# CDCEmu_v4_0.net
KiCad netlist of a schematic drawn in EAGLE
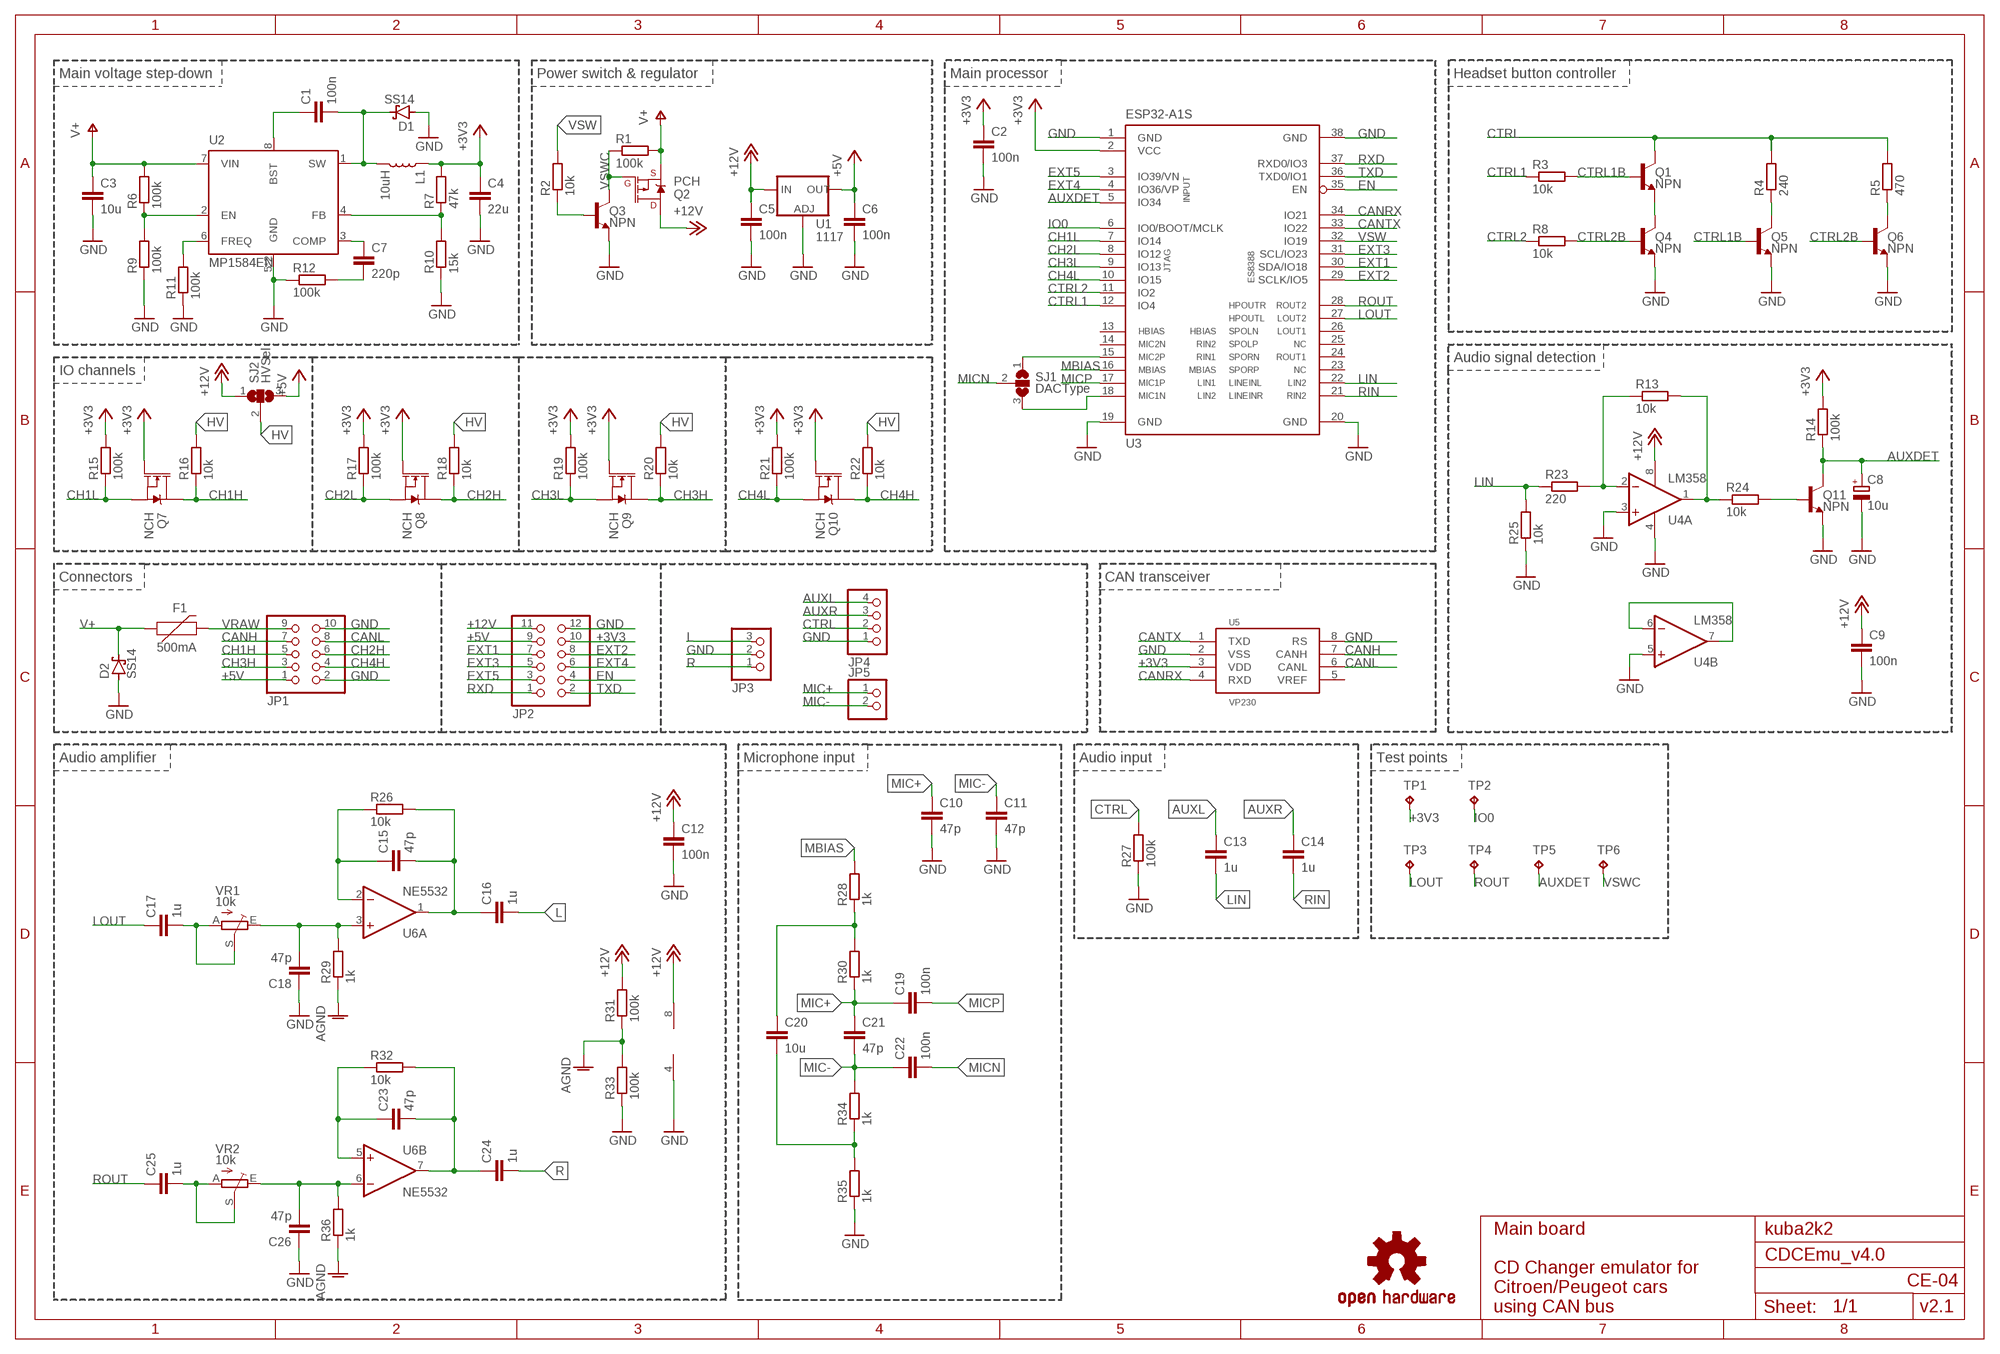
[diagram p0: schematic, sheet 1]

(export (version "E")
  (design (tool "Eeschema 10.0.6"))
  (components
    (comp (ref "C1")
      (value "100n")
      (footprint "eagle-import:C0805")
      (libsource (lib "eagle-import") (part "C-EUC0805"))
    )
    (comp (ref "C2")
      (value "100n")
      (footprint "eagle-import:C0805")
      (libsource (lib "eagle-import") (part "C-EUC0805"))
    )
    (comp (ref "C3")
      (value "10u")
      (footprint "eagle-import:C1206")
      (libsource (lib "eagle-import") (part "C-EUC1206"))
    )
    (comp (ref "C4")
      (value "22u")
      (footprint "eagle-import:C1206")
      (libsource (lib "eagle-import") (part "C-EUC1206"))
    )
    (comp (ref "C5")
      (value "100n")
      (footprint "eagle-import:C0805")
      (libsource (lib "eagle-import") (part "C-EUC0805"))
    )
    (comp (ref "C6")
      (value "100n")
      (footprint "eagle-import:C0805")
      (libsource (lib "eagle-import") (part "C-EUC0805"))
    )
    (comp (ref "C7")
      (value "220p")
      (footprint "eagle-import:C0805")
      (libsource (lib "eagle-import") (part "C-EUC0805"))
    )
    (comp (ref "C8")
      (value "10u")
      (footprint "eagle-import:C1206-POL")
      (libsource (lib "eagle-import") (part "CPOL-EUC1206"))
    )
    (comp (ref "C9")
      (value "100n")
      (footprint "eagle-import:C0805")
      (libsource (lib "eagle-import") (part "C-EUC0805"))
    )
    (comp (ref "C10")
      (value "47p")
      (footprint "eagle-import:C0805")
      (libsource (lib "eagle-import") (part "C-EUC0805"))
    )
    (comp (ref "C11")
      (value "47p")
      (footprint "eagle-import:C0805")
      (libsource (lib "eagle-import") (part "C-EUC0805"))
    )
    (comp (ref "C12")
      (value "100n")
      (footprint "eagle-import:C0805")
      (libsource (lib "eagle-import") (part "C-EUC0805"))
    )
    (comp (ref "C13")
      (value "1u")
      (footprint "eagle-import:C0805")
      (libsource (lib "eagle-import") (part "C-EUC0805"))
    )
    (comp (ref "C14")
      (value "1u")
      (footprint "eagle-import:C0805")
      (libsource (lib "eagle-import") (part "C-EUC0805"))
    )
    (comp (ref "C15")
      (value "47p")
      (footprint "eagle-import:C0805")
      (libsource (lib "eagle-import") (part "C-EUC0805"))
    )
    (comp (ref "C16")
      (value "1u")
      (footprint "eagle-import:C0805")
      (libsource (lib "eagle-import") (part "C-EUC0805"))
    )
    (comp (ref "C17")
      (value "1u")
      (footprint "eagle-import:C0805")
      (libsource (lib "eagle-import") (part "C-EUC0805"))
    )
    (comp (ref "C18")
      (value "47p")
      (footprint "eagle-import:C0805")
      (libsource (lib "eagle-import") (part "C-EUC0805"))
    )
    (comp (ref "C19")
      (value "100n")
      (footprint "eagle-import:C0805")
      (libsource (lib "eagle-import") (part "C-EUC0805"))
    )
    (comp (ref "C20")
      (value "10u")
      (footprint "eagle-import:C1206")
      (libsource (lib "eagle-import") (part "C-EUC1206"))
    )
    (comp (ref "C21")
      (value "47p")
      (footprint "eagle-import:C0805")
      (libsource (lib "eagle-import") (part "C-EUC0805"))
    )
    (comp (ref "C22")
      (value "100n")
      (footprint "eagle-import:C0805")
      (libsource (lib "eagle-import") (part "C-EUC0805"))
    )
    (comp (ref "C23")
      (value "47p")
      (footprint "eagle-import:C0805")
      (libsource (lib "eagle-import") (part "C-EUC0805"))
    )
    (comp (ref "C24")
      (value "1u")
      (footprint "eagle-import:C0805")
      (libsource (lib "eagle-import") (part "C-EUC0805"))
    )
    (comp (ref "C25")
      (value "1u")
      (footprint "eagle-import:C0805")
      (libsource (lib "eagle-import") (part "C-EUC0805"))
    )
    (comp (ref "C26")
      (value "47p")
      (footprint "eagle-import:C0805")
      (libsource (lib "eagle-import") (part "C-EUC0805"))
    )
    (comp (ref "D1")
      (value "SS14")
      (footprint "eagle-import:DO-214AC")
      (libsource (lib "eagle-import") (part "SS14"))
    )
    (comp (ref "D2")
      (value "SS14")
      (footprint "eagle-import:DO-214AC")
      (libsource (lib "eagle-import") (part "SS14"))
    )
    (comp (ref "F1")
      (value "500mA")
      (footprint "eagle-import:0805")
      (libsource (lib "eagle-import") (part "PPTC_6V500MA"))
    )
    (comp (ref "JP1")
      (value "PINHD-2X5/90")
      (footprint "eagle-import:2X05_90")
      (libsource (lib "eagle-import") (part "PINHD-2X5/90"))
    )
    (comp (ref "JP2")
      (value "PINHD-2X6/90")
      (footprint "eagle-import:2X06_90")
      (libsource (lib "eagle-import") (part "PINHD-2X6/90"))
    )
    (comp (ref "JP3")
      (value "PINHD-1X3/90")
      (footprint "eagle-import:1X03_90")
      (libsource (lib "eagle-import") (part "PINHD-1X3/90"))
    )
    (comp (ref "JP4")
      (value "PINHD-1X4/90")
      (footprint "eagle-import:1X04_90")
      (libsource (lib "eagle-import") (part "PINHD-1X4/90"))
    )
    (comp (ref "JP5")
      (value "PINHD-1X2/90")
      (footprint "eagle-import:1X02_90")
      (libsource (lib "eagle-import") (part "PINHD-1X2/90"))
    )
    (comp (ref "L1")
      (value "10uH")
      (footprint "eagle-import:CR75")
      (libsource (lib "eagle-import") (part "INDUCTOR-CR75-68UH"))
    )
    (comp (ref "Q1")
      (value "NPN")
      (footprint "eagle-import:SOT23-3")
      (libsource (lib "eagle-import") (part "TRANS_NPN-MMBTA42"))
    )
    (comp (ref "Q2")
      (value "PCH")
      (footprint "eagle-import:SOT23-3")
      (libsource (lib "eagle-import") (part "MOSFET_PCH-IRLML2244"))
    )
    (comp (ref "Q3")
      (value "NPN")
      (footprint "eagle-import:SOT23-3")
      (libsource (lib "eagle-import") (part "TRANS_NPN-MMBTA42"))
    )
    (comp (ref "Q4")
      (value "NPN")
      (footprint "eagle-import:SOT23-3")
      (libsource (lib "eagle-import") (part "TRANS_NPN-MMBTA42"))
    )
    (comp (ref "Q5")
      (value "NPN")
      (footprint "eagle-import:SOT23-3")
      (libsource (lib "eagle-import") (part "TRANS_NPN-MMBTA42"))
    )
    (comp (ref "Q6")
      (value "NPN")
      (footprint "eagle-import:SOT23-3")
      (libsource (lib "eagle-import") (part "TRANS_NPN-MMBTA42"))
    )
    (comp (ref "Q7")
      (value "NCH")
      (footprint "eagle-import:SOT23-3")
      (libsource (lib "eagle-import") (part "MOSFET-NCH-AO3404A"))
    )
    (comp (ref "Q8")
      (value "NCH")
      (footprint "eagle-import:SOT23-3")
      (libsource (lib "eagle-import") (part "MOSFET-NCH-AO3404A"))
    )
    (comp (ref "Q9")
      (value "NCH")
      (footprint "eagle-import:SOT23-3")
      (libsource (lib "eagle-import") (part "MOSFET-NCH-AO3404A"))
    )
    (comp (ref "Q10")
      (value "NCH")
      (footprint "eagle-import:SOT23-3")
      (libsource (lib "eagle-import") (part "MOSFET-NCH-AO3404A"))
    )
    (comp (ref "Q11")
      (value "NPN")
      (footprint "eagle-import:SOT23-3")
      (libsource (lib "eagle-import") (part "TRANS_NPN-MMBTA42"))
    )
    (comp (ref "R1")
      (value "100k")
      (footprint "eagle-import:R0805")
      (libsource (lib "eagle-import") (part "R-EU_R0805"))
    )
    (comp (ref "R2")
      (value "10k")
      (footprint "eagle-import:R0805")
      (libsource (lib "eagle-import") (part "R-EU_R0805"))
    )
    (comp (ref "R3")
      (value "10k")
      (footprint "eagle-import:R0805")
      (libsource (lib "eagle-import") (part "R-EU_R0805"))
    )
    (comp (ref "R4")
      (value "240")
      (footprint "eagle-import:R0805")
      (libsource (lib "eagle-import") (part "R-EU_R0805"))
    )
    (comp (ref "R5")
      (value "470")
      (footprint "eagle-import:R0805")
      (libsource (lib "eagle-import") (part "R-EU_R0805"))
    )
    (comp (ref "R6")
      (value "100k")
      (footprint "eagle-import:R0805")
      (libsource (lib "eagle-import") (part "R-EU_R0805"))
    )
    (comp (ref "R7")
      (value "47k")
      (footprint "eagle-import:R0805")
      (libsource (lib "eagle-import") (part "R-EU_R0805"))
    )
    (comp (ref "R8")
      (value "10k")
      (footprint "eagle-import:R0805")
      (libsource (lib "eagle-import") (part "R-EU_R0805"))
    )
    (comp (ref "R9")
      (value "100k")
      (footprint "eagle-import:R0805")
      (libsource (lib "eagle-import") (part "R-EU_R0805"))
    )
    (comp (ref "R10")
      (value "15k")
      (footprint "eagle-import:R0805")
      (libsource (lib "eagle-import") (part "R-EU_R0805"))
    )
    (comp (ref "R11")
      (value "100k")
      (footprint "eagle-import:R0805")
      (libsource (lib "eagle-import") (part "R-EU_R0805"))
    )
    (comp (ref "R12")
      (value "100k")
      (footprint "eagle-import:R0805")
      (libsource (lib "eagle-import") (part "R-EU_R0805"))
    )
    (comp (ref "R13")
      (value "10k")
      (footprint "eagle-import:R0805")
      (libsource (lib "eagle-import") (part "R-EU_R0805"))
    )
    (comp (ref "R14")
      (value "100k")
      (footprint "eagle-import:R0805")
      (libsource (lib "eagle-import") (part "R-EU_R0805"))
    )
    (comp (ref "R15")
      (value "100k")
      (footprint "eagle-import:R0805")
      (libsource (lib "eagle-import") (part "R-EU_R0805"))
    )
    (comp (ref "R16")
      (value "10k")
      (footprint "eagle-import:R0805")
      (libsource (lib "eagle-import") (part "R-EU_R0805"))
    )
    (comp (ref "R17")
      (value "100k")
      (footprint "eagle-import:R0805")
      (libsource (lib "eagle-import") (part "R-EU_R0805"))
    )
    (comp (ref "R18")
      (value "10k")
      (footprint "eagle-import:R0805")
      (libsource (lib "eagle-import") (part "R-EU_R0805"))
    )
    (comp (ref "R19")
      (value "100k")
      (footprint "eagle-import:R0805")
      (libsource (lib "eagle-import") (part "R-EU_R0805"))
    )
    (comp (ref "R20")
      (value "10k")
      (footprint "eagle-import:R0805")
      (libsource (lib "eagle-import") (part "R-EU_R0805"))
    )
    (comp (ref "R21")
      (value "100k")
      (footprint "eagle-import:R0805")
      (libsource (lib "eagle-import") (part "R-EU_R0805"))
    )
    (comp (ref "R22")
      (value "10k")
      (footprint "eagle-import:R0805")
      (libsource (lib "eagle-import") (part "R-EU_R0805"))
    )
    (comp (ref "R23")
      (value "220")
      (footprint "eagle-import:R0805")
      (libsource (lib "eagle-import") (part "R-EU_R0805"))
    )
    (comp (ref "R24")
      (value "10k")
      (footprint "eagle-import:R0805")
      (libsource (lib "eagle-import") (part "R-EU_R0805"))
    )
    (comp (ref "R25")
      (value "10k")
      (footprint "eagle-import:R0805")
      (libsource (lib "eagle-import") (part "R-EU_R0805"))
    )
    (comp (ref "R26")
      (value "10k")
      (footprint "eagle-import:R0805")
      (libsource (lib "eagle-import") (part "R-EU_R0805"))
    )
    (comp (ref "R27")
      (value "100k")
      (footprint "eagle-import:R0805")
      (libsource (lib "eagle-import") (part "R-EU_R0805"))
    )
    (comp (ref "R28")
      (value "1k")
      (footprint "eagle-import:R0805")
      (libsource (lib "eagle-import") (part "R-EU_R0805"))
    )
    (comp (ref "R29")
      (value "1k")
      (footprint "eagle-import:R0805")
      (libsource (lib "eagle-import") (part "R-EU_R0805"))
    )
    (comp (ref "R30")
      (value "1k")
      (footprint "eagle-import:R0805")
      (libsource (lib "eagle-import") (part "R-EU_R0805"))
    )
    (comp (ref "R31")
      (value "100k")
      (footprint "eagle-import:R0805")
      (libsource (lib "eagle-import") (part "R-EU_R0805"))
    )
    (comp (ref "R32")
      (value "10k")
      (footprint "eagle-import:R0805")
      (libsource (lib "eagle-import") (part "R-EU_R0805"))
    )
    (comp (ref "R33")
      (value "100k")
      (footprint "eagle-import:R0805")
      (libsource (lib "eagle-import") (part "R-EU_R0805"))
    )
    (comp (ref "R34")
      (value "1k")
      (footprint "eagle-import:R0805")
      (libsource (lib "eagle-import") (part "R-EU_R0805"))
    )
    (comp (ref "R35")
      (value "1k")
      (footprint "eagle-import:R0805")
      (libsource (lib "eagle-import") (part "R-EU_R0805"))
    )
    (comp (ref "R36")
      (value "1k")
      (footprint "eagle-import:R0805")
      (libsource (lib "eagle-import") (part "R-EU_R0805"))
    )
    (comp (ref "SJ1")
      (value "DACType")
      (footprint "eagle-import:SJ_2")
      (libsource (lib "eagle-import") (part "SJ2W"))
    )
    (comp (ref "SJ2")
      (value "HVSel")
      (footprint "eagle-import:SJ_2")
      (libsource (lib "eagle-import") (part "SJ2W"))
    )
    (comp (ref "TP1")
      (value "TPB1,27")
      (footprint "eagle-import:B1,27")
      (libsource (lib "eagle-import") (part "TPB1,27"))
    )
    (comp (ref "TP2")
      (value "TPB1,27")
      (footprint "eagle-import:B1,27")
      (libsource (lib "eagle-import") (part "TPB1,27"))
    )
    (comp (ref "TP3")
      (value "TPB1,27")
      (footprint "eagle-import:B1,27")
      (libsource (lib "eagle-import") (part "TPB1,27"))
    )
    (comp (ref "TP4")
      (value "TPB1,27")
      (footprint "eagle-import:B1,27")
      (libsource (lib "eagle-import") (part "TPB1,27"))
    )
    (comp (ref "TP5")
      (value "TPB1,27")
      (footprint "eagle-import:B1,27")
      (libsource (lib "eagle-import") (part "TPB1,27"))
    )
    (comp (ref "TP6")
      (value "TPB1,27")
      (footprint "eagle-import:B1,27")
      (libsource (lib "eagle-import") (part "TPB1,27"))
    )
    (comp (ref "U$1")
      (value "OSHW-LOGO")
      (footprint "eagle-import:OSHWLOGO_TOP_0.2_OUTLINE")
      (libsource (lib "eagle-import") (part "OSHW-LOGO"))
    )
    (comp (ref "U1")
      (value "1117")
      (footprint "eagle-import:SOT223")
      (libsource (lib "eagle-import") (part "V_REG_LM1117SOT223"))
    )
    (comp (ref "U2")
      (value "MP1584EN")
      (footprint "eagle-import:SO08-PAD")
      (libsource (lib "eagle-import") (part "MP1584EN_-PAD"))
    )
    (comp (ref "U3")
      (value "ESP32-A1S")
      (footprint "eagle-import:ESP32-A1S")
      (libsource (lib "eagle-import") (part "ESP32-A1S"))
    )
    (comp (ref "U4")
      (value "LM358")
      (footprint "eagle-import:SO08")
      (libsource (lib "eagle-import") (part "LM358D"))
    )
    (comp (ref "U5")
      (value "VP230")
      (footprint "eagle-import:SO08")
      (libsource (lib "eagle-import") (part "SN65HVD230"))
    )
    (comp (ref "U6")
      (value "NE5532")
      (footprint "eagle-import:SO08")
      (libsource (lib "eagle-import") (part "LM358D"))
    )
    (comp (ref "VR1")
      (value "10k")
      (footprint "eagle-import:CA6V")
      (libsource (lib "eagle-import") (part "TRIM_EU-CA6V"))
    )
    (comp (ref "VR2")
      (value "10k")
      (footprint "eagle-import:CA6V")
      (libsource (lib "eagle-import") (part "TRIM_EU-CA6V"))
    )
  )
  (nets
    (net (code "1") (name "+3V3") (class "Default")
      (node (ref "C2") (pin "1") (pinfunction "1_1") (pintype "passive"))
      (node (ref "C4") (pin "1") (pinfunction "1_1") (pintype "passive"))
      (node (ref "JP2") (pin "10") (pinfunction "10_10") (pintype "passive"))
      (node (ref "L1") (pin "P$1") (pinfunction "1_P$1") (pintype "passive"))
      (node (ref "Q10") (pin "1") (pinfunction "G_1") (pintype "bidirectional"))
      (node (ref "Q7") (pin "1") (pinfunction "G_1") (pintype "bidirectional"))
      (node (ref "Q8") (pin "1") (pinfunction "G_1") (pintype "bidirectional"))
      (node (ref "Q9") (pin "1") (pinfunction "G_1") (pintype "bidirectional"))
      (node (ref "R14") (pin "2") (pinfunction "2_2") (pintype "passive"))
      (node (ref "R15") (pin "2") (pinfunction "2_2") (pintype "passive"))
      (node (ref "R17") (pin "2") (pinfunction "2_2") (pintype "passive"))
      (node (ref "R19") (pin "2") (pinfunction "2_2") (pintype "passive"))
      (node (ref "R21") (pin "2") (pinfunction "2_2") (pintype "passive"))
      (node (ref "R7") (pin "2") (pinfunction "2_2") (pintype "passive"))
      (node (ref "TP1") (pin "TP") (pinfunction "TP_TP") (pintype "input"))
      (node (ref "U3") (pin "2") (pinfunction "VCC_2") (pintype "power_in"))
      (node (ref "U5") (pin "3") (pinfunction "VDD_3") (pintype "power_in"))
    )
    (net (code "2") (name "+5V") (class "Default")
      (node (ref "C6") (pin "1") (pinfunction "1_1") (pintype "passive"))
      (node (ref "JP1") (pin "1") (pinfunction "1_1") (pintype "passive"))
      (node (ref "JP2") (pin "9") (pinfunction "9_9") (pintype "passive"))
      (node (ref "SJ2") (pin "3") (pinfunction "3_3") (pintype "passive"))
      (node (ref "U1") (pin "2") (pinfunction "OUT_2") (pintype "output"))
      (node (ref "U1") (pin "4") (pinfunction "OUT_4") (pintype "output"))
    )
    (net (code "3") (name "+12V") (class "Default")
      (node (ref "C12") (pin "1") (pinfunction "1_1") (pintype "passive"))
      (node (ref "C5") (pin "1") (pinfunction "1_1") (pintype "passive"))
      (node (ref "C9") (pin "1") (pinfunction "1_1") (pintype "passive"))
      (node (ref "JP2") (pin "11") (pinfunction "11_11") (pintype "passive"))
      (node (ref "Q2") (pin "3") (pinfunction "D_3") (pintype "bidirectional"))
      (node (ref "R31") (pin "2") (pinfunction "2_2") (pintype "passive"))
      (node (ref "SJ2") (pin "1") (pinfunction "1_1") (pintype "passive"))
      (node (ref "U1") (pin "3") (pinfunction "IN_3") (pintype "input"))
      (node (ref "U4") (pin "8") (pinfunction "V+_8") (pintype "power_in"))
      (node (ref "U6") (pin "8") (pinfunction "V+_8") (pintype "power_in"))
    )
    (net (code "4") (name "/AUXDET") (class "Default")
      (node (ref "C8") (pin "1") (pinfunction "+_1") (pintype "passive"))
      (node (ref "Q11") (pin "3") (pinfunction "C_3") (pintype "passive"))
      (node (ref "R14") (pin "1") (pinfunction "1_1") (pintype "passive"))
      (node (ref "TP5") (pin "TP") (pinfunction "TP_TP") (pintype "input"))
      (node (ref "U3") (pin "5") (pinfunction "IO34_5") (pintype "bidirectional"))
    )
    (net (code "5") (name "/CANH") (class "Default")
      (node (ref "JP1") (pin "7") (pinfunction "7_7") (pintype "passive"))
      (node (ref "U5") (pin "7") (pinfunction "CANH_7") (pintype "bidirectional"))
    )
    (net (code "6") (name "/CANL") (class "Default")
      (node (ref "JP1") (pin "8") (pinfunction "8_8") (pintype "passive"))
      (node (ref "U5") (pin "6") (pinfunction "CANL_6") (pintype "bidirectional"))
    )
    (net (code "7") (name "/CANRX") (class "Default")
      (node (ref "U3") (pin "34") (pinfunction "IO21_34") (pintype "bidirectional"))
      (node (ref "U5") (pin "4") (pinfunction "RXD_4") (pintype "output"))
    )
    (net (code "8") (name "/CANTX") (class "Default")
      (node (ref "U3") (pin "33") (pinfunction "IO22_33") (pintype "bidirectional"))
      (node (ref "U5") (pin "1") (pinfunction "TXD_1") (pintype "input"))
    )
    (net (code "9") (name "/CH1H") (class "Default")
      (node (ref "JP1") (pin "5") (pinfunction "5_5") (pintype "passive"))
      (node (ref "Q7") (pin "3") (pinfunction "D_3") (pintype "bidirectional"))
      (node (ref "R16") (pin "1") (pinfunction "1_1") (pintype "passive"))
    )
    (net (code "10") (name "/CH1L") (class "Default")
      (node (ref "Q7") (pin "2") (pinfunction "S_2") (pintype "bidirectional"))
      (node (ref "R15") (pin "1") (pinfunction "1_1") (pintype "passive"))
      (node (ref "U3") (pin "7") (pinfunction "IO14_7") (pintype "bidirectional"))
    )
    (net (code "11") (name "/CH2H") (class "Default")
      (node (ref "JP1") (pin "6") (pinfunction "6_6") (pintype "passive"))
      (node (ref "Q8") (pin "3") (pinfunction "D_3") (pintype "bidirectional"))
      (node (ref "R18") (pin "1") (pinfunction "1_1") (pintype "passive"))
    )
    (net (code "12") (name "/CH2L") (class "Default")
      (node (ref "Q8") (pin "2") (pinfunction "S_2") (pintype "bidirectional"))
      (node (ref "R17") (pin "1") (pinfunction "1_1") (pintype "passive"))
      (node (ref "U3") (pin "8") (pinfunction "IO12_8") (pintype "bidirectional"))
    )
    (net (code "13") (name "/CH3H") (class "Default")
      (node (ref "JP1") (pin "3") (pinfunction "3_3") (pintype "passive"))
      (node (ref "Q9") (pin "3") (pinfunction "D_3") (pintype "bidirectional"))
      (node (ref "R20") (pin "1") (pinfunction "1_1") (pintype "passive"))
    )
    (net (code "14") (name "/CH3L") (class "Default")
      (node (ref "Q9") (pin "2") (pinfunction "S_2") (pintype "bidirectional"))
      (node (ref "R19") (pin "1") (pinfunction "1_1") (pintype "passive"))
      (node (ref "U3") (pin "9") (pinfunction "IO13_9") (pintype "bidirectional"))
    )
    (net (code "15") (name "/CH4H") (class "Default")
      (node (ref "JP1") (pin "4") (pinfunction "4_4") (pintype "passive"))
      (node (ref "Q10") (pin "3") (pinfunction "D_3") (pintype "bidirectional"))
      (node (ref "R22") (pin "1") (pinfunction "1_1") (pintype "passive"))
    )
    (net (code "16") (name "/CH4L") (class "Default")
      (node (ref "Q10") (pin "2") (pinfunction "S_2") (pintype "bidirectional"))
      (node (ref "R21") (pin "1") (pinfunction "1_1") (pintype "passive"))
      (node (ref "U3") (pin "10") (pinfunction "IO15_10") (pintype "bidirectional"))
    )
    (net (code "17") (name "/CTRL1") (class "Default")
      (node (ref "R3") (pin "1") (pinfunction "1_1") (pintype "passive"))
      (node (ref "U3") (pin "12") (pinfunction "IO4_12") (pintype "bidirectional"))
    )
    (net (code "18") (name "/CTRL1B") (class "Default")
      (node (ref "Q1") (pin "1") (pinfunction "B_1") (pintype "passive"))
      (node (ref "Q5") (pin "1") (pinfunction "B_1") (pintype "passive"))
      (node (ref "R3") (pin "2") (pinfunction "2_2") (pintype "passive"))
    )
    (net (code "19") (name "/CTRL2") (class "Default")
      (node (ref "R8") (pin "1") (pinfunction "1_1") (pintype "passive"))
      (node (ref "U3") (pin "11") (pinfunction "IO2_11") (pintype "bidirectional"))
    )
    (net (code "20") (name "/CTRL2B") (class "Default")
      (node (ref "Q4") (pin "1") (pinfunction "B_1") (pintype "passive"))
      (node (ref "Q6") (pin "1") (pinfunction "B_1") (pintype "passive"))
      (node (ref "R8") (pin "2") (pinfunction "2_2") (pintype "passive"))
    )
    (net (code "21") (name "/EN") (class "Default")
      (node (ref "JP2") (pin "4") (pinfunction "4_4") (pintype "passive"))
      (node (ref "U3") (pin "35") (pinfunction "EN_35") (pintype "bidirectional"))
    )
    (net (code "22") (name "/EXT1") (class "Default")
      (node (ref "JP2") (pin "7") (pinfunction "7_7") (pintype "passive"))
      (node (ref "U3") (pin "30") (pinfunction "SDA/IO18_30") (pintype "bidirectional"))
    )
    (net (code "23") (name "/EXT2") (class "Default")
      (node (ref "JP2") (pin "8") (pinfunction "8_8") (pintype "passive"))
      (node (ref "U3") (pin "29") (pinfunction "SCLK/IO5_29") (pintype "bidirectional"))
    )
    (net (code "24") (name "/EXT3") (class "Default")
      (node (ref "JP2") (pin "5") (pinfunction "5_5") (pintype "passive"))
      (node (ref "U3") (pin "31") (pinfunction "SCL/IO23_31") (pintype "bidirectional"))
    )
    (net (code "25") (name "/EXT4") (class "Default")
      (node (ref "JP2") (pin "6") (pinfunction "6_6") (pintype "passive"))
      (node (ref "U3") (pin "4") (pinfunction "IO36/VP_4") (pintype "passive"))
    )
    (net (code "26") (name "/EXT5") (class "Default")
      (node (ref "JP2") (pin "3") (pinfunction "3_3") (pintype "passive"))
      (node (ref "U3") (pin "3") (pinfunction "IO39/VN_3") (pintype "passive"))
    )
    (net (code "27") (name "/IO0") (class "Default")
      (node (ref "TP2") (pin "TP") (pinfunction "TP_TP") (pintype "input"))
      (node (ref "U3") (pin "6") (pinfunction "IO0/BOOT/MCLK_6") (pintype "bidirectional"))
    )
    (net (code "28") (name "/LOUT") (class "Default")
      (node (ref "C17") (pin "1") (pinfunction "1_1") (pintype "passive"))
      (node (ref "TP3") (pin "TP") (pinfunction "TP_TP") (pintype "input"))
      (node (ref "U3") (pin "27") (pinfunction "HPOUTL/LOUT2_27") (pintype "bidirectional"))
    )
    (net (code "29") (name "/ROUT") (class "Default")
      (node (ref "C25") (pin "1") (pinfunction "1_1") (pintype "passive"))
      (node (ref "TP4") (pin "TP") (pinfunction "TP_TP") (pintype "input"))
      (node (ref "U3") (pin "28") (pinfunction "HPOUTR/ROUT2_28") (pintype "bidirectional"))
    )
    (net (code "30") (name "/RXD") (class "Default")
      (node (ref "JP2") (pin "1") (pinfunction "1_1") (pintype "passive"))
      (node (ref "U3") (pin "37") (pinfunction "RXD0/IO3_37") (pintype "bidirectional"))
    )
    (net (code "31") (name "/TXD") (class "Default")
      (node (ref "JP2") (pin "2") (pinfunction "2_2") (pintype "passive"))
      (node (ref "U3") (pin "36") (pinfunction "TXD0/IO1_36") (pintype "bidirectional"))
    )
    (net (code "32") (name "/VRAW") (class "Default")
      (node (ref "F1") (pin "2") (pinfunction "2_2") (pintype "bidirectional"))
      (node (ref "JP1") (pin "9") (pinfunction "9_9") (pintype "passive"))
    )
    (net (code "33") (name "/VSWC") (class "Default")
      (node (ref "Q2") (pin "1") (pinfunction "G_1") (pintype "bidirectional"))
      (node (ref "Q3") (pin "3") (pinfunction "C_3") (pintype "passive"))
      (node (ref "R1") (pin "1") (pinfunction "1_1") (pintype "passive"))
      (node (ref "TP6") (pin "TP") (pinfunction "TP_TP") (pintype "input"))
    )
    (net (code "34") (name "AGND") (class "Default")
      (node (ref "R29") (pin "1") (pinfunction "1_1") (pintype "passive"))
      (node (ref "R31") (pin "1") (pinfunction "1_1") (pintype "passive"))
      (node (ref "R33") (pin "2") (pinfunction "2_2") (pintype "passive"))
      (node (ref "R36") (pin "1") (pinfunction "1_1") (pintype "passive"))
    )
    (net (code "35") (name "AUXL") (class "Default")
      (node (ref "C13") (pin "1") (pinfunction "1_1") (pintype "passive"))
      (node (ref "JP4") (pin "4") (pinfunction "4_4") (pintype "passive"))
    )
    (net (code "36") (name "AUXR") (class "Default")
      (node (ref "C14") (pin "1") (pinfunction "1_1") (pintype "passive"))
      (node (ref "JP4") (pin "3") (pinfunction "3_3") (pintype "passive"))
    )
    (net (code "37") (name "CTRL") (class "Default")
      (node (ref "JP4") (pin "2") (pinfunction "2_2") (pintype "passive"))
      (node (ref "Q1") (pin "3") (pinfunction "C_3") (pintype "passive"))
      (node (ref "R27") (pin "2") (pinfunction "2_2") (pintype "passive"))
      (node (ref "R4") (pin "2") (pinfunction "2_2") (pintype "passive"))
      (node (ref "R5") (pin "2") (pinfunction "2_2") (pintype "passive"))
    )
    (net (code "38") (name "GND") (class "Default")
      (node (ref "C10") (pin "2") (pinfunction "2_2") (pintype "passive"))
      (node (ref "C11") (pin "2") (pinfunction "2_2") (pintype "passive"))
      (node (ref "C12") (pin "2") (pinfunction "2_2") (pintype "passive"))
      (node (ref "C18") (pin "1") (pinfunction "1_1") (pintype "passive"))
      (node (ref "C2") (pin "2") (pinfunction "2_2") (pintype "passive"))
      (node (ref "C26") (pin "1") (pinfunction "1_1") (pintype "passive"))
      (node (ref "C3") (pin "2") (pinfunction "2_2") (pintype "passive"))
      (node (ref "C4") (pin "2") (pinfunction "2_2") (pintype "passive"))
      (node (ref "C5") (pin "2") (pinfunction "2_2") (pintype "passive"))
      (node (ref "C6") (pin "2") (pinfunction "2_2") (pintype "passive"))
      (node (ref "C8") (pin "2") (pinfunction "-_2") (pintype "passive"))
      (node (ref "C9") (pin "2") (pinfunction "2_2") (pintype "passive"))
      (node (ref "D1") (pin "A") (pinfunction "A_A") (pintype "passive"))
      (node (ref "D2") (pin "A") (pinfunction "A_A") (pintype "passive"))
      (node (ref "JP1") (pin "10") (pinfunction "10_10") (pintype "passive"))
      (node (ref "JP1") (pin "2") (pinfunction "2_2") (pintype "passive"))
      (node (ref "JP2") (pin "12") (pinfunction "12_12") (pintype "passive"))
      (node (ref "JP3") (pin "2") (pinfunction "2_2") (pintype "passive"))
      (node (ref "JP4") (pin "1") (pinfunction "1_1") (pintype "passive"))
      (node (ref "Q11") (pin "2") (pinfunction "E_2") (pintype "passive"))
      (node (ref "Q3") (pin "2") (pinfunction "E_2") (pintype "passive"))
      (node (ref "Q4") (pin "2") (pinfunction "E_2") (pintype "passive"))
      (node (ref "Q5") (pin "2") (pinfunction "E_2") (pintype "passive"))
      (node (ref "Q6") (pin "2") (pinfunction "E_2") (pintype "passive"))
      (node (ref "R10") (pin "1") (pinfunction "1_1") (pintype "passive"))
      (node (ref "R11") (pin "1") (pinfunction "1_1") (pintype "passive"))
      (node (ref "R12") (pin "1") (pinfunction "1_1") (pintype "passive"))
      (node (ref "R25") (pin "1") (pinfunction "1_1") (pintype "passive"))
      (node (ref "R27") (pin "1") (pinfunction "1_1") (pintype "passive"))
      (node (ref "R33") (pin "1") (pinfunction "1_1") (pintype "passive"))
      (node (ref "R35") (pin "1") (pinfunction "1_1") (pintype "passive"))
      (node (ref "R9") (pin "1") (pinfunction "1_1") (pintype "passive"))
      (node (ref "U1") (pin "1") (pinfunction "ADJ_1") (pintype "input"))
      (node (ref "U2") (pin "5") (pinfunction "GND_5") (pintype "power_in"))
      (node (ref "U2") (pin "PAD") (pinfunction "GND_PAD") (pintype "power_in"))
      (node (ref "U3") (pin "1") (pinfunction "GND_1") (pintype "power_in"))
      (node (ref "U3") (pin "19") (pinfunction "GND_19") (pintype "power_in"))
      (node (ref "U3") (pin "20") (pinfunction "GND_20") (pintype "power_in"))
      (node (ref "U3") (pin "38") (pinfunction "GND_38") (pintype "power_in"))
      (node (ref "U4") (pin "3") (pinfunction "+IN_3") (pintype "input"))
      (node (ref "U4") (pin "4") (pinfunction "V-_4") (pintype "power_in"))
      (node (ref "U4") (pin "5") (pinfunction "+IN_5") (pintype "input"))
      (node (ref "U5") (pin "2") (pinfunction "VSS_2") (pintype "power_in"))
      (node (ref "U5") (pin "8") (pinfunction "RS_8") (pintype "input"))
      (node (ref "U6") (pin "4") (pinfunction "V-_4") (pintype "power_in"))
    )
    (net (code "39") (name "HV") (class "Default")
      (node (ref "R16") (pin "2") (pinfunction "2_2") (pintype "passive"))
      (node (ref "R18") (pin "2") (pinfunction "2_2") (pintype "passive"))
      (node (ref "R20") (pin "2") (pinfunction "2_2") (pintype "passive"))
      (node (ref "R22") (pin "2") (pinfunction "2_2") (pintype "passive"))
      (node (ref "SJ2") (pin "2") (pinfunction "2_2") (pintype "passive"))
    )
    (net (code "40") (name "L") (class "Default")
      (node (ref "C16") (pin "2") (pinfunction "2_2") (pintype "passive"))
      (node (ref "JP3") (pin "3") (pinfunction "3_3") (pintype "passive"))
    )
    (net (code "41") (name "LIN") (class "Default")
      (node (ref "C13") (pin "2") (pinfunction "2_2") (pintype "passive"))
      (node (ref "R23") (pin "1") (pinfunction "1_1") (pintype "passive"))
      (node (ref "R25") (pin "2") (pinfunction "2_2") (pintype "passive"))
      (node (ref "U3") (pin "22") (pinfunction "LINEINL/LIN2_22") (pintype "bidirectional"))
    )
    (net (code "42") (name "MBIAS") (class "Default")
      (node (ref "R28") (pin "2") (pinfunction "2_2") (pintype "passive"))
      (node (ref "U3") (pin "16") (pinfunction "MBIAS_16") (pintype "bidirectional"))
    )
    (net (code "43") (name "MIC+") (class "Default")
      (node (ref "C10") (pin "1") (pinfunction "1_1") (pintype "passive"))
      (node (ref "C19") (pin "1") (pinfunction "1_1") (pintype "passive"))
      (node (ref "C21") (pin "1") (pinfunction "1_1") (pintype "passive"))
      (node (ref "JP5") (pin "1") (pinfunction "1_1") (pintype "passive"))
      (node (ref "R30") (pin "1") (pinfunction "1_1") (pintype "passive"))
    )
    (net (code "44") (name "MIC-") (class "Default")
      (node (ref "C11") (pin "1") (pinfunction "1_1") (pintype "passive"))
      (node (ref "C21") (pin "2") (pinfunction "2_2") (pintype "passive"))
      (node (ref "C22") (pin "1") (pinfunction "1_1") (pintype "passive"))
      (node (ref "JP5") (pin "2") (pinfunction "2_2") (pintype "passive"))
      (node (ref "R34") (pin "2") (pinfunction "2_2") (pintype "passive"))
    )
    (net (code "45") (name "MICN") (class "Default")
      (node (ref "C22") (pin "2") (pinfunction "2_2") (pintype "passive"))
      (node (ref "SJ1") (pin "2") (pinfunction "2_2") (pintype "passive"))
    )
    (net (code "46") (name "MICP") (class "Default")
      (node (ref "C19") (pin "2") (pinfunction "2_2") (pintype "passive"))
      (node (ref "U3") (pin "17") (pinfunction "MIC1P/LIN1_17") (pintype "bidirectional"))
    )
    (net (code "47") (name "Net-(C7-Pad2)") (class "Default")
      (node (ref "C7") (pin "2") (pinfunction "2_2") (pintype "passive"))
      (node (ref "R12") (pin "2") (pinfunction "2_2") (pintype "passive"))
    )
    (net (code "48") (name "Net-(C17-Pad2)") (class "Default")
      (node (ref "C17") (pin "2") (pinfunction "2_2") (pintype "passive"))
      (node (ref "VR1") (pin "A") (pinfunction "A_A") (pintype "passive"))
      (node (ref "VR1") (pin "S") (pinfunction "S_S") (pintype "passive"))
    )
    (net (code "49") (name "Net-(C20-Pad1)") (class "Default")
      (node (ref "C20") (pin "1") (pinfunction "1_1") (pintype "passive"))
      (node (ref "R28") (pin "1") (pinfunction "1_1") (pintype "passive"))
      (node (ref "R30") (pin "2") (pinfunction "2_2") (pintype "passive"))
    )
    (net (code "50") (name "Net-(C20-Pad2)") (class "Default")
      (node (ref "C20") (pin "2") (pinfunction "2_2") (pintype "passive"))
      (node (ref "R34") (pin "1") (pinfunction "1_1") (pintype "passive"))
      (node (ref "R35") (pin "2") (pinfunction "2_2") (pintype "passive"))
    )
    (net (code "51") (name "Net-(C25-Pad2)") (class "Default")
      (node (ref "C25") (pin "2") (pinfunction "2_2") (pintype "passive"))
      (node (ref "VR2") (pin "A") (pinfunction "A_A") (pintype "passive"))
      (node (ref "VR2") (pin "S") (pinfunction "S_S") (pintype "passive"))
    )
    (net (code "52") (name "Net-(L1-2)") (class "Default")
      (node (ref "C1") (pin "2") (pinfunction "2_2") (pintype "passive"))
      (node (ref "D1") (pin "C") (pinfunction "C_C") (pintype "passive"))
      (node (ref "L1") (pin "P$2") (pinfunction "2_P$2") (pintype "passive"))
      (node (ref "U2") (pin "1") (pinfunction "SW_1") (pintype "output"))
    )
    (net (code "53") (name "Net-(Q1-E)") (class "Default")
      (node (ref "Q1") (pin "2") (pinfunction "E_2") (pintype "passive"))
      (node (ref "Q4") (pin "3") (pinfunction "C_3") (pintype "passive"))
    )
    (net (code "54") (name "Net-(Q3-B)") (class "Default")
      (node (ref "Q3") (pin "1") (pinfunction "B_1") (pintype "passive"))
      (node (ref "R2") (pin "1") (pinfunction "1_1") (pintype "passive"))
    )
    (net (code "55") (name "Net-(Q5-C)") (class "Default")
      (node (ref "Q5") (pin "3") (pinfunction "C_3") (pintype "passive"))
      (node (ref "R4") (pin "1") (pinfunction "1_1") (pintype "passive"))
    )
    (net (code "56") (name "Net-(Q6-C)") (class "Default")
      (node (ref "Q6") (pin "3") (pinfunction "C_3") (pintype "passive"))
      (node (ref "R5") (pin "1") (pinfunction "1_1") (pintype "passive"))
    )
    (net (code "57") (name "Net-(Q11-B)") (class "Default")
      (node (ref "Q11") (pin "1") (pinfunction "B_1") (pintype "passive"))
      (node (ref "R24") (pin "2") (pinfunction "2_2") (pintype "passive"))
    )
    (net (code "58") (name "Net-(U2-BST)") (class "Default")
      (node (ref "C1") (pin "1") (pinfunction "1_1") (pintype "passive"))
      (node (ref "U2") (pin "8") (pinfunction "BST_8") (pintype "input"))
    )
    (net (code "59") (name "Net-(U2-COMP)") (class "Default")
      (node (ref "C7") (pin "1") (pinfunction "1_1") (pintype "passive"))
      (node (ref "U2") (pin "3") (pinfunction "COMP_3") (pintype "input"))
    )
    (net (code "60") (name "Net-(U2-EN)") (class "Default")
      (node (ref "R6") (pin "1") (pinfunction "1_1") (pintype "passive"))
      (node (ref "R9") (pin "2") (pinfunction "2_2") (pintype "passive"))
      (node (ref "U2") (pin "2") (pinfunction "EN_2") (pintype "input"))
    )
    (net (code "61") (name "Net-(U2-FB)") (class "Default")
      (node (ref "R10") (pin "2") (pinfunction "2_2") (pintype "passive"))
      (node (ref "R7") (pin "1") (pinfunction "1_1") (pintype "passive"))
      (node (ref "U2") (pin "4") (pinfunction "FB_4") (pintype "input"))
    )
    (net (code "62") (name "Net-(U2-FREQ)") (class "Default")
      (node (ref "R11") (pin "2") (pinfunction "2_2") (pintype "passive"))
      (node (ref "U2") (pin "6") (pinfunction "FREQ_6") (pintype "input"))
    )
    (net (code "63") (name "Net-(U3-MIC1N{slash}LIN2)") (class "Default")
      (node (ref "SJ1") (pin "3") (pinfunction "3_3") (pintype "passive"))
      (node (ref "U3") (pin "18") (pinfunction "MIC1N/LIN2_18") (pintype "bidirectional"))
    )
    (net (code "64") (name "Net-(U3-MIC2P{slash}RIN1)") (class "Default")
      (node (ref "SJ1") (pin "1") (pinfunction "1_1") (pintype "passive"))
      (node (ref "U3") (pin "15") (pinfunction "MIC2P/RIN1_15") (pintype "bidirectional"))
    )
    (net (code "65") (name "Net-(U4A--IN)") (class "Default")
      (node (ref "R13") (pin "1") (pinfunction "1_1") (pintype "passive"))
      (node (ref "R23") (pin "2") (pinfunction "2_2") (pintype "passive"))
      (node (ref "U4") (pin "2") (pinfunction "-IN_2") (pintype "input"))
    )
    (net (code "66") (name "Net-(U4A-OUT)") (class "Default")
      (node (ref "R13") (pin "2") (pinfunction "2_2") (pintype "passive"))
      (node (ref "R24") (pin "1") (pinfunction "1_1") (pintype "passive"))
      (node (ref "U4") (pin "1") (pinfunction "OUT_1") (pintype "output"))
    )
    (net (code "67") (name "Net-(U4B--IN)") (class "Default")
      (node (ref "U4") (pin "6") (pinfunction "-IN_6") (pintype "input"))
      (node (ref "U4") (pin "7") (pinfunction "OUT_7") (pintype "output"))
    )
    (net (code "68") (name "Net-(U6A-+IN)") (class "Default")
      (node (ref "C18") (pin "2") (pinfunction "2_2") (pintype "passive"))
      (node (ref "R29") (pin "2") (pinfunction "2_2") (pintype "passive"))
      (node (ref "U6") (pin "3") (pinfunction "+IN_3") (pintype "input"))
      (node (ref "VR1") (pin "E") (pinfunction "E_E") (pintype "passive"))
    )
    (net (code "69") (name "Net-(U6A--IN)") (class "Default")
      (node (ref "C15") (pin "1") (pinfunction "1_1") (pintype "passive"))
      (node (ref "R26") (pin "1") (pinfunction "1_1") (pintype "passive"))
      (node (ref "U6") (pin "2") (pinfunction "-IN_2") (pintype "input"))
    )
    (net (code "70") (name "Net-(U6A-OUT)") (class "Default")
      (node (ref "C15") (pin "2") (pinfunction "2_2") (pintype "passive"))
      (node (ref "C16") (pin "1") (pinfunction "1_1") (pintype "passive"))
      (node (ref "R26") (pin "2") (pinfunction "2_2") (pintype "passive"))
      (node (ref "U6") (pin "1") (pinfunction "OUT_1") (pintype "output"))
    )
    (net (code "71") (name "Net-(U6B-+IN)") (class "Default")
      (node (ref "C23") (pin "1") (pinfunction "1_1") (pintype "passive"))
      (node (ref "R32") (pin "1") (pinfunction "1_1") (pintype "passive"))
      (node (ref "U6") (pin "5") (pinfunction "+IN_5") (pintype "input"))
    )
    (net (code "72") (name "Net-(U6B--IN)") (class "Default")
      (node (ref "C26") (pin "2") (pinfunction "2_2") (pintype "passive"))
      (node (ref "R36") (pin "2") (pinfunction "2_2") (pintype "passive"))
      (node (ref "U6") (pin "6") (pinfunction "-IN_6") (pintype "input"))
      (node (ref "VR2") (pin "E") (pinfunction "E_E") (pintype "passive"))
    )
    (net (code "73") (name "Net-(U6B-OUT)") (class "Default")
      (node (ref "C23") (pin "2") (pinfunction "2_2") (pintype "passive"))
      (node (ref "C24") (pin "1") (pinfunction "1_1") (pintype "passive"))
      (node (ref "R32") (pin "2") (pinfunction "2_2") (pintype "passive"))
      (node (ref "U6") (pin "7") (pinfunction "OUT_7") (pintype "output"))
    )
    (net (code "74") (name "R") (class "Default")
      (node (ref "C24") (pin "2") (pinfunction "2_2") (pintype "passive"))
      (node (ref "JP3") (pin "1") (pinfunction "1_1") (pintype "passive"))
    )
    (net (code "75") (name "RIN") (class "Default")
      (node (ref "C14") (pin "2") (pinfunction "2_2") (pintype "passive"))
      (node (ref "U3") (pin "21") (pinfunction "LINEINR/RIN2_21") (pintype "bidirectional"))
    )
    (net (code "76") (name "V+") (class "Default")
      (node (ref "C3") (pin "1") (pinfunction "1_1") (pintype "passive"))
      (node (ref "D2") (pin "C") (pinfunction "C_C") (pintype "passive"))
      (node (ref "F1") (pin "1") (pinfunction "1_1") (pintype "bidirectional"))
      (node (ref "Q2") (pin "2") (pinfunction "S_2") (pintype "bidirectional"))
      (node (ref "R1") (pin "2") (pinfunction "2_2") (pintype "passive"))
      (node (ref "R6") (pin "2") (pinfunction "2_2") (pintype "passive"))
      (node (ref "U2") (pin "7") (pinfunction "VIN_7") (pintype "power_in"))
    )
    (net (code "77") (name "VSW") (class "Default")
      (node (ref "R2") (pin "2") (pinfunction "2_2") (pintype "passive"))
      (node (ref "U3") (pin "32") (pinfunction "IO19_32") (pintype "bidirectional"))
    )
    (net (code "78") (name "unconnected-(U3-HBIAS-Pad13)") (class "Default")
      (node (ref "U3") (pin "13") (pinfunction "HBIAS_13") (pintype "bidirectional"))
    )
    (net (code "79") (name "unconnected-(U3-MIC2N{slash}RIN2-Pad14)") (class "Default")
      (node (ref "U3") (pin "14") (pinfunction "MIC2N/RIN2_14") (pintype "bidirectional"))
    )
    (net (code "80") (name "unconnected-(U3-SPOLN{slash}LOUT1-Pad26)") (class "Default")
      (node (ref "U3") (pin "26") (pinfunction "SPOLN/LOUT1_26") (pintype "bidirectional"))
    )
    (net (code "81") (name "unconnected-(U3-SPOLP{slash}NC-Pad25)") (class "Default")
      (node (ref "U3") (pin "25") (pinfunction "SPOLP/NC_25") (pintype "bidirectional"))
    )
    (net (code "82") (name "unconnected-(U3-SPORN{slash}ROUT1-Pad24)") (class "Default")
      (node (ref "U3") (pin "24") (pinfunction "SPORN/ROUT1_24") (pintype "bidirectional"))
    )
    (net (code "83") (name "unconnected-(U3-SPORP{slash}NC-Pad23)") (class "Default")
      (node (ref "U3") (pin "23") (pinfunction "SPORP/NC_23") (pintype "bidirectional"))
    )
    (net (code "84") (name "unconnected-(U5-VREF-Pad5)") (class "Default")
      (node (ref "U5") (pin "5") (pinfunction "VREF_5") (pintype "passive"))
    )
  )
)
